# Transceiver_KW1_Sachs.net
KiCad netlist of a schematic drawn in EAGLE
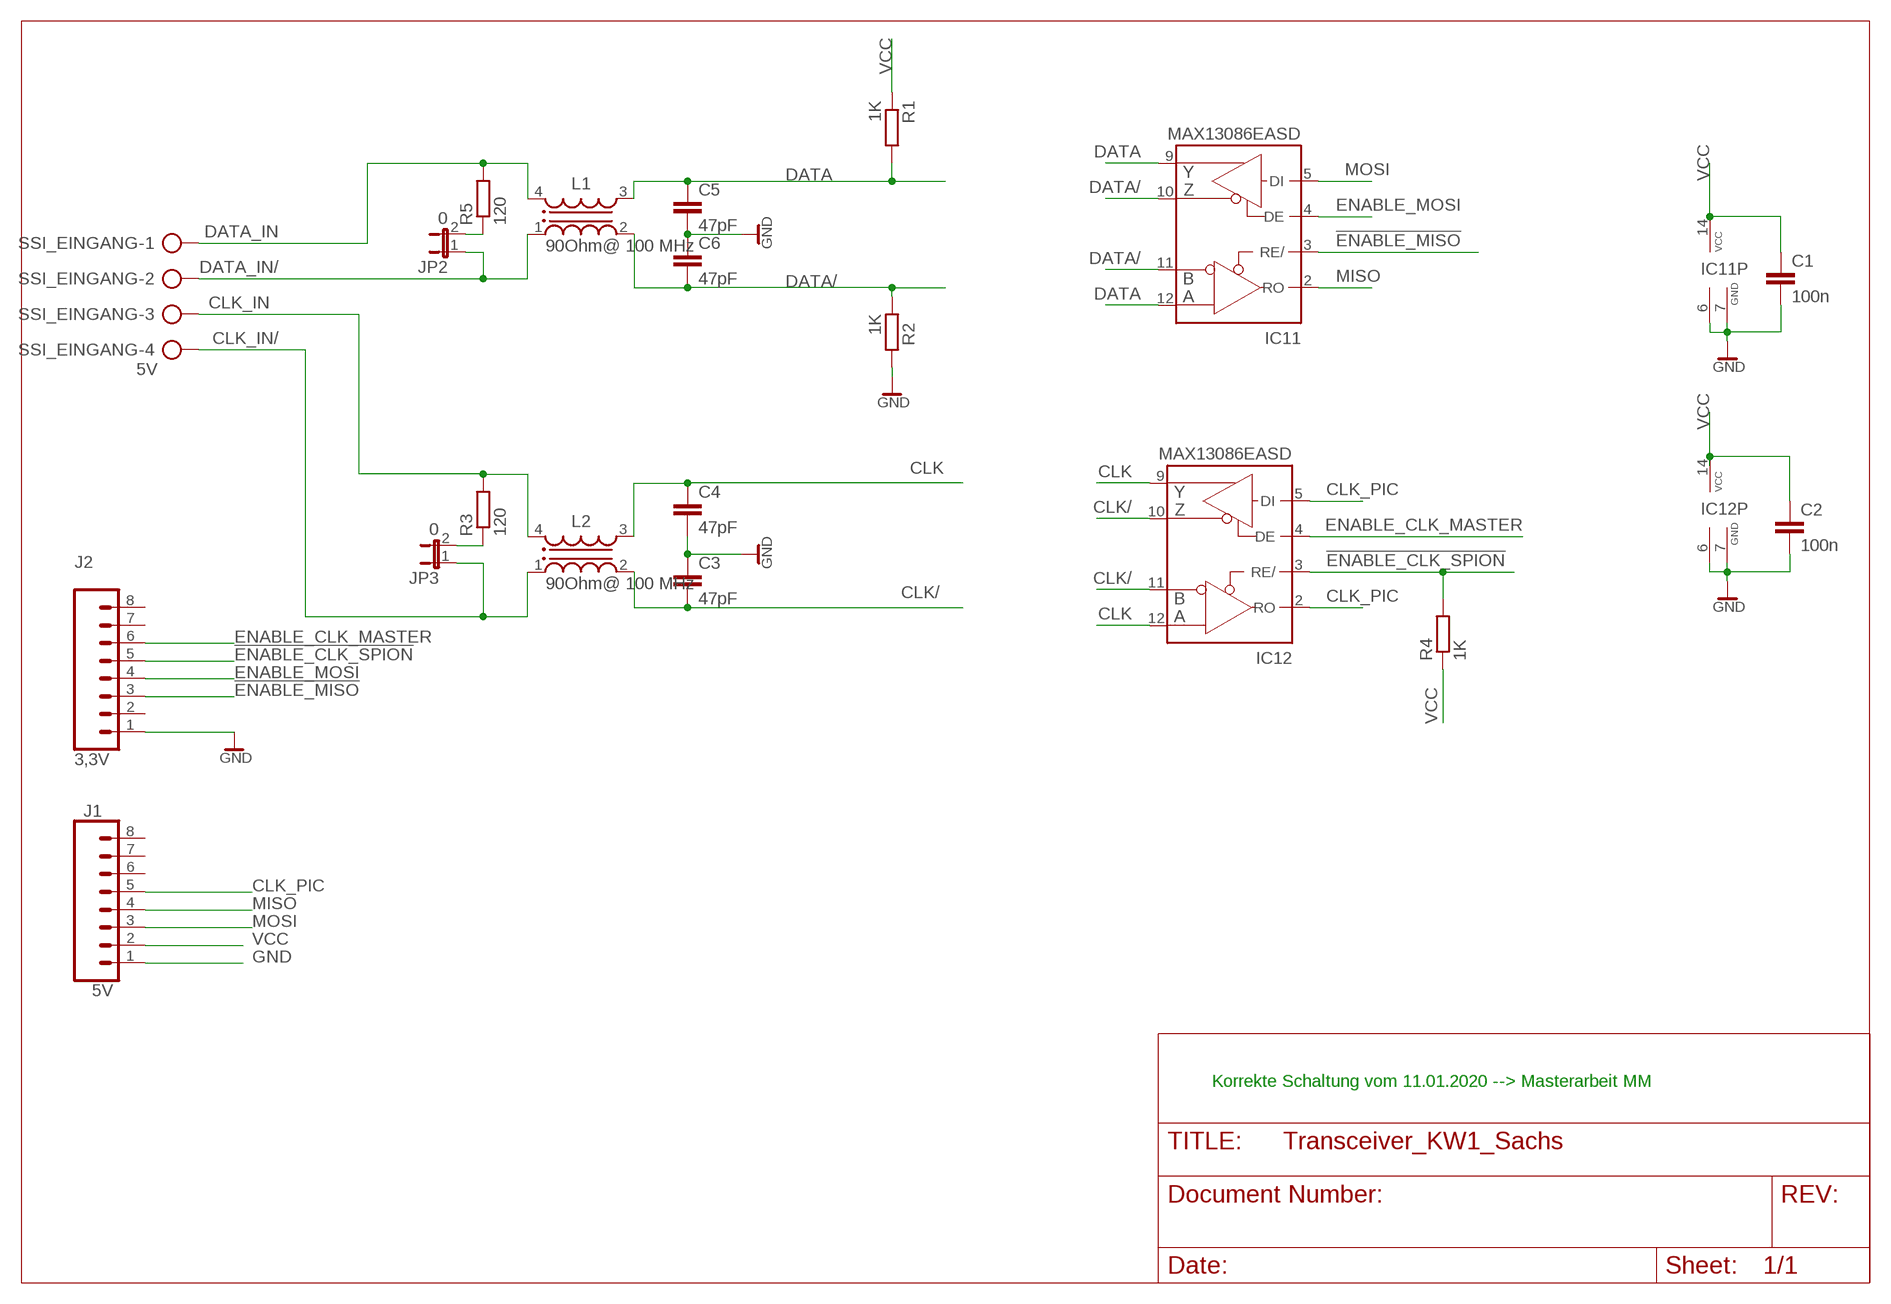
[diagram p0: schematic, sheet 1]

(export (version "E")
  (design (tool "Eeschema 10.0.6"))
  (components
    (comp (ref "C1")
      (value "100n")
      (footprint "eagle-import:C0603")
      (libsource (lib "eagle-import") (part "C-EUC0603"))
    )
    (comp (ref "C2")
      (value "100n")
      (footprint "eagle-import:C0603")
      (libsource (lib "eagle-import") (part "C-EUC0603"))
    )
    (comp (ref "C3")
      (value "47pF")
      (footprint "eagle-import:C0603")
      (libsource (lib "eagle-import") (part "C-EUC0603"))
    )
    (comp (ref "C4")
      (value "47pF")
      (footprint "eagle-import:C0603")
      (libsource (lib "eagle-import") (part "C-EUC0603"))
    )
    (comp (ref "C5")
      (value "47pF")
      (footprint "eagle-import:C0603")
      (libsource (lib "eagle-import") (part "C-EUC0603"))
    )
    (comp (ref "C6")
      (value "47pF")
      (footprint "eagle-import:C0603")
      (libsource (lib "eagle-import") (part "C-EUC0603"))
    )
    (comp (ref "IC11")
      (value "MAX13086EASD")
      (footprint "eagle-import:SO14")
      (libsource (lib "eagle-import") (part "MAX489CPDSO14"))
    )
    (comp (ref "IC12")
      (value "MAX13086EASD")
      (footprint "eagle-import:SO14")
      (libsource (lib "eagle-import") (part "MAX489CPDSO14"))
    )
    (comp (ref "J1")
      (value "5V")
      (footprint "eagle-import:1X08")
      (libsource (lib "eagle-import") (part "CONN_08{dblquote}"))
    )
    (comp (ref "J2")
      (value "3,3V")
      (footprint "eagle-import:1X08")
      (libsource (lib "eagle-import") (part "CONN_08{dblquote}"))
    )
    (comp (ref "JP2")
      (value "0")
      (footprint "eagle-import:JP1")
      (libsource (lib "eagle-import") (part "JP1E"))
    )
    (comp (ref "JP3")
      (value "0")
      (footprint "eagle-import:JP1")
      (libsource (lib "eagle-import") (part "JP1E"))
    )
    (comp (ref "L1")
      (value "90Ohm@ 100 MHz")
      (footprint "eagle-import:WE-CNSW_0805")
      (libsource (lib "eagle-import") (part "WE-CNSW_0805_744231091"))
    )
    (comp (ref "L2")
      (value "90Ohm@ 100 MHz")
      (footprint "eagle-import:WE-CNSW_0805")
      (libsource (lib "eagle-import") (part "WE-CNSW_0805_744231091"))
    )
    (comp (ref "R1")
      (value "1K")
      (footprint "eagle-import:R0603")
      (libsource (lib "eagle-import") (part "R-EU_R0603"))
    )
    (comp (ref "R2")
      (value "1K")
      (footprint "eagle-import:R0603")
      (libsource (lib "eagle-import") (part "R-EU_R0603"))
    )
    (comp (ref "R3")
      (value "120")
      (footprint "eagle-import:R0603")
      (libsource (lib "eagle-import") (part "R-EU_R0603"))
    )
    (comp (ref "R4")
      (value "1K")
      (footprint "eagle-import:R0603")
      (libsource (lib "eagle-import") (part "R-EU_R0603"))
    )
    (comp (ref "R5")
      (value "120")
      (footprint "eagle-import:R0603")
      (libsource (lib "eagle-import") (part "R-EU_R0603"))
    )
    (comp (ref "SSI_EINGANG")
      (value "5V")
      (footprint "eagle-import:AK500_4-H")
      (libsource (lib "eagle-import") (part "AK500/4-H"))
    )
  )
  (nets
    (net (code "1") (name "/CLK") (class "Default")
      (node (ref "C4") (pin "1") (pinfunction "1_1") (pintype "passive"))
      (node (ref "IC12") (pin "12") (pinfunction "A_12") (pintype "passive"))
      (node (ref "IC12") (pin "9") (pinfunction "Y_9") (pintype "passive"))
      (node (ref "L2") (pin "3") (pinfunction "2_3") (pintype "passive"))
    )
    (net (code "2") (name "/CLK_IN") (class "Default")
      (node (ref "L2") (pin "4") (pinfunction "1_4") (pintype "passive"))
      (node (ref "R3") (pin "2") (pinfunction "2_2") (pintype "passive"))
      (node (ref "SSI_EINGANG") (pin "3") (pinfunction "KL_3") (pintype "passive"))
    )
    (net (code "3") (name "/CLK_IN{slash}") (class "Default")
      (node (ref "JP3") (pin "1") (pinfunction "1_1") (pintype "passive"))
      (node (ref "L2") (pin "1") (pinfunction "4_1") (pintype "passive"))
      (node (ref "SSI_EINGANG") (pin "4") (pinfunction "KL_4") (pintype "passive"))
    )
    (net (code "4") (name "/CLK_PIC") (class "Default")
      (node (ref "IC12") (pin "2") (pinfunction "RO_2") (pintype "output"))
      (node (ref "IC12") (pin "5") (pinfunction "DI_5") (pintype "input"))
      (node (ref "J1") (pin "5") (pinfunction "5_5") (pintype "passive"))
    )
    (net (code "5") (name "/CLK{slash}") (class "Default")
      (node (ref "C3") (pin "2") (pinfunction "2_2") (pintype "passive"))
      (node (ref "IC12") (pin "10") (pinfunction "Z_10") (pintype "passive"))
      (node (ref "IC12") (pin "11") (pinfunction "B_11") (pintype "passive"))
      (node (ref "L2") (pin "2") (pinfunction "3_2") (pintype "passive"))
    )
    (net (code "6") (name "/DATA") (class "Default")
      (node (ref "C5") (pin "1") (pinfunction "1_1") (pintype "passive"))
      (node (ref "IC11") (pin "12") (pinfunction "A_12") (pintype "passive"))
      (node (ref "IC11") (pin "9") (pinfunction "Y_9") (pintype "passive"))
      (node (ref "L1") (pin "3") (pinfunction "2_3") (pintype "passive"))
      (node (ref "R1") (pin "2") (pinfunction "2_2") (pintype "passive"))
    )
    (net (code "7") (name "/DATA_IN") (class "Default")
      (node (ref "L1") (pin "4") (pinfunction "1_4") (pintype "passive"))
      (node (ref "R5") (pin "2") (pinfunction "2_2") (pintype "passive"))
      (node (ref "SSI_EINGANG") (pin "1") (pinfunction "KL_1") (pintype "passive"))
    )
    (net (code "8") (name "/DATA_IN{slash}") (class "Default")
      (node (ref "JP2") (pin "1") (pinfunction "1_1") (pintype "passive"))
      (node (ref "L1") (pin "1") (pinfunction "4_1") (pintype "passive"))
      (node (ref "SSI_EINGANG") (pin "2") (pinfunction "KL_2") (pintype "passive"))
    )
    (net (code "9") (name "/DATA{slash}") (class "Default")
      (node (ref "C6") (pin "2") (pinfunction "2_2") (pintype "passive"))
      (node (ref "IC11") (pin "10") (pinfunction "Z_10") (pintype "passive"))
      (node (ref "IC11") (pin "11") (pinfunction "B_11") (pintype "passive"))
      (node (ref "L1") (pin "2") (pinfunction "3_2") (pintype "passive"))
      (node (ref "R2") (pin "1") (pinfunction "1_1") (pintype "passive"))
    )
    (net (code "10") (name "/ENABLE_CLK_MASTER") (class "Default")
      (node (ref "IC12") (pin "4") (pinfunction "DE_4") (pintype "input"))
      (node (ref "J2") (pin "6") (pinfunction "6_6") (pintype "passive"))
    )
    (net (code "11") (name "/ENABLE_MOSI") (class "Default")
      (node (ref "IC11") (pin "4") (pinfunction "DE_4") (pintype "input"))
      (node (ref "J2") (pin "4") (pinfunction "4_4") (pintype "passive"))
    )
    (net (code "12") (name "/MISO") (class "Default")
      (node (ref "IC11") (pin "2") (pinfunction "RO_2") (pintype "output"))
      (node (ref "J1") (pin "4") (pinfunction "4_4") (pintype "passive"))
    )
    (net (code "13") (name "/MOSI") (class "Default")
      (node (ref "IC11") (pin "5") (pinfunction "DI_5") (pintype "input"))
      (node (ref "J1") (pin "3") (pinfunction "3_3") (pintype "passive"))
    )
    (net (code "14") (name "/VCC") (class "Default")
      (node (ref "C1") (pin "1") (pinfunction "1_1") (pintype "passive"))
      (node (ref "C2") (pin "1") (pinfunction "1_1") (pintype "passive"))
      (node (ref "IC11") (pin "14") (pinfunction "VCC_14") (pintype "power_in"))
      (node (ref "IC12") (pin "14") (pinfunction "VCC_14") (pintype "power_in"))
      (node (ref "J1") (pin "2") (pinfunction "2_2") (pintype "passive"))
      (node (ref "R1") (pin "1") (pinfunction "1_1") (pintype "passive"))
      (node (ref "R4") (pin "1") (pinfunction "1_1") (pintype "passive"))
    )
    (net (code "15") (name "/~{ENABLE_CLK_SPION}") (class "Default")
      (node (ref "IC12") (pin "3") (pinfunction "RE/_3") (pintype "input"))
      (node (ref "J2") (pin "5") (pinfunction "5_5") (pintype "passive"))
      (node (ref "R4") (pin "2") (pinfunction "2_2") (pintype "passive"))
    )
    (net (code "16") (name "/~{ENABLE_MISO}") (class "Default")
      (node (ref "IC11") (pin "3") (pinfunction "RE/_3") (pintype "input"))
      (node (ref "J2") (pin "3") (pinfunction "3_3") (pintype "passive"))
    )
    (net (code "17") (name "GND") (class "Default")
      (node (ref "C1") (pin "2") (pinfunction "2_2") (pintype "passive"))
      (node (ref "C2") (pin "2") (pinfunction "2_2") (pintype "passive"))
      (node (ref "C3") (pin "1") (pinfunction "1_1") (pintype "passive"))
      (node (ref "C4") (pin "2") (pinfunction "2_2") (pintype "passive"))
      (node (ref "C5") (pin "2") (pinfunction "2_2") (pintype "passive"))
      (node (ref "C6") (pin "1") (pinfunction "1_1") (pintype "passive"))
      (node (ref "IC11") (pin "6") (pinfunction "GND_6") (pintype "power_in"))
      (node (ref "IC11") (pin "7") (pinfunction "GND_7") (pintype "power_in"))
      (node (ref "IC12") (pin "6") (pinfunction "GND_6") (pintype "power_in"))
      (node (ref "IC12") (pin "7") (pinfunction "GND_7") (pintype "power_in"))
      (node (ref "J1") (pin "1") (pinfunction "1_1") (pintype "passive"))
      (node (ref "J2") (pin "1") (pinfunction "1_1") (pintype "passive"))
      (node (ref "R2") (pin "2") (pinfunction "2_2") (pintype "passive"))
    )
    (net (code "18") (name "Net-(JP2-Pad2)") (class "Default")
      (node (ref "JP2") (pin "2") (pinfunction "2_2") (pintype "passive"))
      (node (ref "R5") (pin "1") (pinfunction "1_1") (pintype "passive"))
    )
    (net (code "19") (name "Net-(JP3-Pad2)") (class "Default")
      (node (ref "JP3") (pin "2") (pinfunction "2_2") (pintype "passive"))
      (node (ref "R3") (pin "1") (pinfunction "1_1") (pintype "passive"))
    )
    (net (code "20") (name "unconnected-(J1-Pad6)") (class "Default")
      (node (ref "J1") (pin "6") (pinfunction "6_6") (pintype "passive"))
    )
    (net (code "21") (name "unconnected-(J1-Pad7)") (class "Default")
      (node (ref "J1") (pin "7") (pinfunction "7_7") (pintype "passive"))
    )
    (net (code "22") (name "unconnected-(J1-Pad8)") (class "Default")
      (node (ref "J1") (pin "8") (pinfunction "8_8") (pintype "passive"))
    )
    (net (code "23") (name "unconnected-(J2-Pad2)") (class "Default")
      (node (ref "J2") (pin "2") (pinfunction "2_2") (pintype "passive"))
    )
    (net (code "24") (name "unconnected-(J2-Pad7)") (class "Default")
      (node (ref "J2") (pin "7") (pinfunction "7_7") (pintype "passive"))
    )
    (net (code "25") (name "unconnected-(J2-Pad8)") (class "Default")
      (node (ref "J2") (pin "8") (pinfunction "8_8") (pintype "passive"))
    )
  )
)
